# Adafruit_NeoParticle24.net
KiCad netlist of a schematic drawn in EAGLE
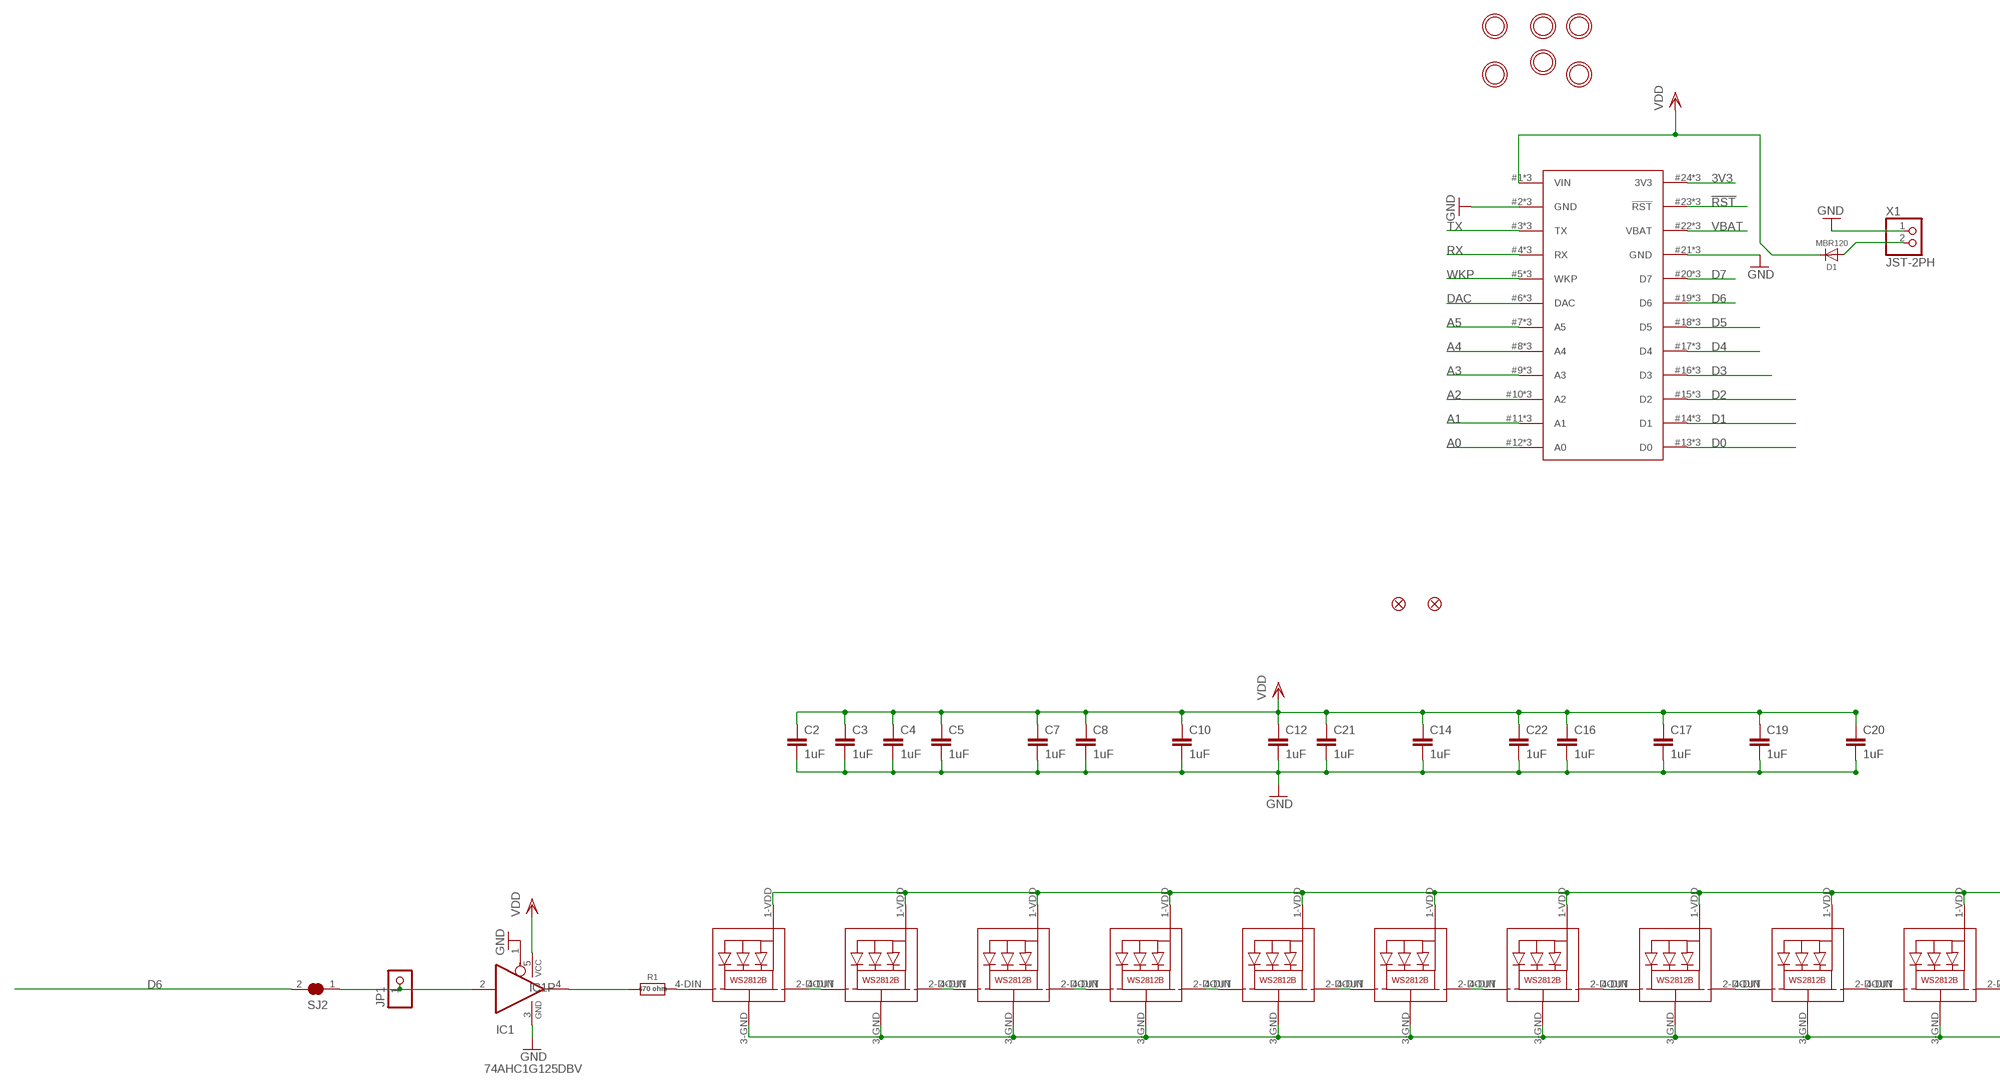
[diagram p0: schematic, sheet 1, part 1 of 2]
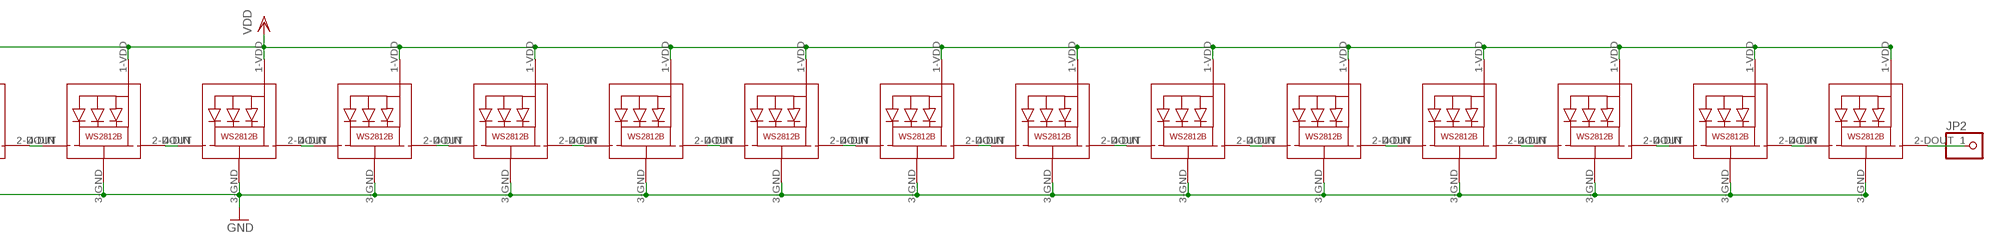
[diagram p1: schematic, sheet 1, part 2 of 2]

(export (version "E")
  (design (tool "Eeschema 10.0.6"))
  (components
    (comp (ref "C2")
      (value "1uF")
      (footprint "eagle-import:C0603")
      (libsource (lib "eagle-import") (part "C-EUC0603"))
    )
    (comp (ref "C3")
      (value "1uF")
      (footprint "eagle-import:C0603")
      (libsource (lib "eagle-import") (part "C-EUC0603"))
    )
    (comp (ref "C4")
      (value "1uF")
      (footprint "eagle-import:C0603")
      (libsource (lib "eagle-import") (part "C-EUC0603"))
    )
    (comp (ref "C5")
      (value "1uF")
      (footprint "eagle-import:C0603")
      (libsource (lib "eagle-import") (part "C-EUC0603"))
    )
    (comp (ref "C7")
      (value "1uF")
      (footprint "eagle-import:C0603")
      (libsource (lib "eagle-import") (part "C-EUC0603"))
    )
    (comp (ref "C8")
      (value "1uF")
      (footprint "eagle-import:C0603")
      (libsource (lib "eagle-import") (part "C-EUC0603"))
    )
    (comp (ref "C10")
      (value "1uF")
      (footprint "eagle-import:C0603")
      (libsource (lib "eagle-import") (part "C-EUC0603"))
    )
    (comp (ref "C12")
      (value "1uF")
      (footprint "eagle-import:C0603")
      (libsource (lib "eagle-import") (part "C-EUC0603"))
    )
    (comp (ref "C14")
      (value "1uF")
      (footprint "eagle-import:C0603")
      (libsource (lib "eagle-import") (part "C-EUC0603"))
    )
    (comp (ref "C16")
      (value "1uF")
      (footprint "eagle-import:C0603")
      (libsource (lib "eagle-import") (part "C-EUC0603"))
    )
    (comp (ref "C17")
      (value "1uF")
      (footprint "eagle-import:C0603")
      (libsource (lib "eagle-import") (part "C-EUC0603"))
    )
    (comp (ref "C19")
      (value "1uF")
      (footprint "eagle-import:C0603")
      (libsource (lib "eagle-import") (part "C-EUC0603"))
    )
    (comp (ref "C20")
      (value "1uF")
      (footprint "eagle-import:C0603")
      (libsource (lib "eagle-import") (part "C-EUC0603"))
    )
    (comp (ref "C21")
      (value "1uF")
      (footprint "eagle-import:C0603")
      (libsource (lib "eagle-import") (part "C-EUC0603"))
    )
    (comp (ref "C22")
      (value "1uF")
      (footprint "eagle-import:C0603")
      (libsource (lib "eagle-import") (part "C-EUC0603"))
    )
    (comp (ref "D1")
      (value "MBR120")
      (footprint "eagle-import:SOD-123")
      (libsource (lib "eagle-import") (part "DIODESOD-123"))
    )
    (comp (ref "FID1")
      (value "FIDUCIAL\"\"")
      (footprint "eagle-import:FIDUCIAL_1MM")
      (libsource (lib "eagle-import") (part "FIDUCIAL{dblquote}{dblquote}"))
    )
    (comp (ref "FID2")
      (value "FIDUCIAL\"\"")
      (footprint "eagle-import:FIDUCIAL_1MM")
      (libsource (lib "eagle-import") (part "FIDUCIAL{dblquote}{dblquote}"))
    )
    (comp (ref "IC1")
      (value "74AHC1G125DBV")
      (footprint "eagle-import:SOT23-5")
      (libsource (lib "eagle-import") (part "741G125DBVAHC"))
    )
    (comp (ref "JP1")
      (value "HEADER-1X1ROUND")
      (footprint "eagle-import:1X01_ROUND")
      (libsource (lib "eagle-import") (part "HEADER-1X1ROUND"))
    )
    (comp (ref "JP2")
      (value "PINHD-1X1CB")
      (footprint "eagle-import:1X01-CLEANBIG")
      (libsource (lib "eagle-import") (part "PINHD-1X1CB"))
    )
    (comp (ref "LED1")
      (value "WS2812B5050")
      (footprint "eagle-import:WS2812B-NARROW")
      (libsource (lib "eagle-import") (part "WS2812B5050-NARROW"))
    )
    (comp (ref "LED2")
      (value "WS2812B5050")
      (footprint "eagle-import:WS2812B-NARROW")
      (libsource (lib "eagle-import") (part "WS2812B5050-NARROW"))
    )
    (comp (ref "LED3")
      (value "WS2812B5050")
      (footprint "eagle-import:WS2812B-NARROW")
      (libsource (lib "eagle-import") (part "WS2812B5050-NARROW"))
    )
    (comp (ref "LED4")
      (value "WS2812B5050")
      (footprint "eagle-import:WS2812B-NARROW")
      (libsource (lib "eagle-import") (part "WS2812B5050-NARROW"))
    )
    (comp (ref "LED5")
      (value "WS2812B5050")
      (footprint "eagle-import:WS2812B-NARROW")
      (libsource (lib "eagle-import") (part "WS2812B5050-NARROW"))
    )
    (comp (ref "LED6")
      (value "WS2812B5050")
      (footprint "eagle-import:WS2812B-NARROW")
      (libsource (lib "eagle-import") (part "WS2812B5050-NARROW"))
    )
    (comp (ref "LED7")
      (value "WS2812B5050")
      (footprint "eagle-import:WS2812B-NARROW")
      (libsource (lib "eagle-import") (part "WS2812B5050-NARROW"))
    )
    (comp (ref "LED8")
      (value "WS2812B5050")
      (footprint "eagle-import:WS2812B-NARROW")
      (libsource (lib "eagle-import") (part "WS2812B5050-NARROW"))
    )
    (comp (ref "LED9")
      (value "WS2812B5050")
      (footprint "eagle-import:WS2812B-NARROW")
      (libsource (lib "eagle-import") (part "WS2812B5050-NARROW"))
    )
    (comp (ref "LED10")
      (value "WS2812B5050")
      (footprint "eagle-import:WS2812B-NARROW")
      (libsource (lib "eagle-import") (part "WS2812B5050-NARROW"))
    )
    (comp (ref "LED11")
      (value "WS2812B5050")
      (footprint "eagle-import:WS2812B-NARROW")
      (libsource (lib "eagle-import") (part "WS2812B5050-NARROW"))
    )
    (comp (ref "LED12")
      (value "WS2812B5050")
      (footprint "eagle-import:WS2812B-NARROW")
      (libsource (lib "eagle-import") (part "WS2812B5050-NARROW"))
    )
    (comp (ref "LED13")
      (value "WS2812B5050")
      (footprint "eagle-import:WS2812B-NARROW")
      (libsource (lib "eagle-import") (part "WS2812B5050-NARROW"))
    )
    (comp (ref "LED14")
      (value "WS2812B5050")
      (footprint "eagle-import:WS2812B-NARROW")
      (libsource (lib "eagle-import") (part "WS2812B5050-NARROW"))
    )
    (comp (ref "LED15")
      (value "WS2812B5050")
      (footprint "eagle-import:WS2812B-NARROW")
      (libsource (lib "eagle-import") (part "WS2812B5050-NARROW"))
    )
    (comp (ref "LED16")
      (value "WS2812B5050")
      (footprint "eagle-import:WS2812B-NARROW")
      (libsource (lib "eagle-import") (part "WS2812B5050-NARROW"))
    )
    (comp (ref "LED17")
      (value "WS2812B5050")
      (footprint "eagle-import:WS2812B-NARROW")
      (libsource (lib "eagle-import") (part "WS2812B5050-NARROW"))
    )
    (comp (ref "LED18")
      (value "WS2812B5050")
      (footprint "eagle-import:WS2812B-NARROW")
      (libsource (lib "eagle-import") (part "WS2812B5050-NARROW"))
    )
    (comp (ref "LED19")
      (value "WS2812B5050")
      (footprint "eagle-import:WS2812B-NARROW")
      (libsource (lib "eagle-import") (part "WS2812B5050-NARROW"))
    )
    (comp (ref "LED20")
      (value "WS2812B5050")
      (footprint "eagle-import:WS2812B-NARROW")
      (libsource (lib "eagle-import") (part "WS2812B5050-NARROW"))
    )
    (comp (ref "LED21")
      (value "WS2812B5050")
      (footprint "eagle-import:WS2812B-NARROW")
      (libsource (lib "eagle-import") (part "WS2812B5050-NARROW"))
    )
    (comp (ref "LED22")
      (value "WS2812B5050")
      (footprint "eagle-import:WS2812B-NARROW")
      (libsource (lib "eagle-import") (part "WS2812B5050-NARROW"))
    )
    (comp (ref "LED23")
      (value "WS2812B5050")
      (footprint "eagle-import:WS2812B-NARROW")
      (libsource (lib "eagle-import") (part "WS2812B5050-NARROW"))
    )
    (comp (ref "LED24")
      (value "WS2812B5050")
      (footprint "eagle-import:WS2812B-NARROW")
      (libsource (lib "eagle-import") (part "WS2812B5050-NARROW"))
    )
    (comp (ref "R1")
      (value "470 ohm")
      (footprint "eagle-import:0603-NO")
      (libsource (lib "eagle-import") (part "RESISTOR_0603_NOOUT"))
    )
    (comp (ref "SJ2")
      (value "SOLDERJUMPER_CLOSED")
      (footprint "eagle-import:SOLDERJUMPER_CLOSEDWIRE")
      (libsource (lib "eagle-import") (part "SOLDERJUMPER_CLOSED"))
    )
    (comp (ref "U$2")
      (value "PHOTON")
      (footprint "eagle-import:SPARK_CORE_STACKABLE")
      (libsource (lib "eagle-import") (part "SPARK_CORE"))
    )
    (comp (ref "U$3")
      (value "MOUNTINGHOLE3.0THIN")
      (footprint "eagle-import:MOUNTINGHOLE_3.0_PLATEDTHIN")
      (libsource (lib "eagle-import") (part "MOUNTINGHOLE3.0THIN"))
    )
    (comp (ref "U$4")
      (value "MOUNTINGHOLE3.0THIN")
      (footprint "eagle-import:MOUNTINGHOLE_3.0_PLATEDTHIN")
      (libsource (lib "eagle-import") (part "MOUNTINGHOLE3.0THIN"))
    )
    (comp (ref "U$5")
      (value "MOUNTINGHOLE3.0THIN")
      (footprint "eagle-import:MOUNTINGHOLE_3.0_PLATEDTHIN")
      (fields (field (name "BOM") "EXCLUDE"))
      (libsource (lib "eagle-import") (part "MOUNTINGHOLE3.0THIN"))
    )
    (comp (ref "U$6")
      (value "MOUNTINGHOLE3.0THIN")
      (footprint "eagle-import:MOUNTINGHOLE_3.0_PLATEDTHIN")
      (fields (field (name "BOM") "EXCLUDE"))
      (libsource (lib "eagle-import") (part "MOUNTINGHOLE3.0THIN"))
    )
    (comp (ref "U$9")
      (value "MOUNTINGHOLE3.0THIN")
      (footprint "eagle-import:MOUNTINGHOLE_3.0_PLATEDTHIN")
      (fields (field (name "BOM") "EXCLUDE"))
      (libsource (lib "eagle-import") (part "MOUNTINGHOLE3.0THIN"))
    )
    (comp (ref "U$10")
      (value "MOUNTINGHOLE3.0THIN")
      (footprint "eagle-import:MOUNTINGHOLE_3.0_PLATEDTHIN")
      (fields (field (name "BOM") "EXCLUDE"))
      (libsource (lib "eagle-import") (part "MOUNTINGHOLE3.0THIN"))
    )
    (comp (ref "X1")
      (value "JST-2PH")
      (footprint "eagle-import:JSTPH2")
      (libsource (lib "eagle-import") (part "CON_JST_PH_2PIN"))
    )
  )
  (nets
    (net (code "1") (name "/3V3") (class "Default")
      (node (ref "U$2") (pin "#24") (pinfunction "3V3_#24") (pintype "power_in"))
      (node (ref "U$2") (pin "24") (pinfunction "3V3_24") (pintype "power_in"))
      (node (ref "U$2") (pin "@24") (pinfunction "3V3_@24") (pintype "power_in"))
    )
    (net (code "2") (name "/A0") (class "Default")
      (node (ref "U$2") (pin "#12") (pinfunction "A0_#12") (pintype "bidirectional"))
      (node (ref "U$2") (pin "12") (pinfunction "A0_12") (pintype "bidirectional"))
      (node (ref "U$2") (pin "@12") (pinfunction "A0_@12") (pintype "bidirectional"))
    )
    (net (code "3") (name "/A1") (class "Default")
      (node (ref "U$2") (pin "#11") (pinfunction "A1_#11") (pintype "bidirectional"))
      (node (ref "U$2") (pin "11") (pinfunction "A1_11") (pintype "bidirectional"))
      (node (ref "U$2") (pin "@11") (pinfunction "A1_@11") (pintype "bidirectional"))
    )
    (net (code "4") (name "/A2") (class "Default")
      (node (ref "U$2") (pin "#10") (pinfunction "A2_#10") (pintype "bidirectional"))
      (node (ref "U$2") (pin "10") (pinfunction "A2_10") (pintype "bidirectional"))
      (node (ref "U$2") (pin "@10") (pinfunction "A2_@10") (pintype "bidirectional"))
    )
    (net (code "5") (name "/A3") (class "Default")
      (node (ref "U$2") (pin "#9") (pinfunction "A3_#9") (pintype "bidirectional"))
      (node (ref "U$2") (pin "9") (pinfunction "A3_9") (pintype "bidirectional"))
      (node (ref "U$2") (pin "@9") (pinfunction "A3_@9") (pintype "bidirectional"))
    )
    (net (code "6") (name "/A4") (class "Default")
      (node (ref "U$2") (pin "#8") (pinfunction "A4_#8") (pintype "bidirectional"))
      (node (ref "U$2") (pin "8") (pinfunction "A4_8") (pintype "bidirectional"))
      (node (ref "U$2") (pin "@8") (pinfunction "A4_@8") (pintype "bidirectional"))
    )
    (net (code "7") (name "/A5") (class "Default")
      (node (ref "U$2") (pin "#7") (pinfunction "A5_#7") (pintype "bidirectional"))
      (node (ref "U$2") (pin "7") (pinfunction "A5_7") (pintype "bidirectional"))
      (node (ref "U$2") (pin "@7") (pinfunction "A5_@7") (pintype "bidirectional"))
    )
    (net (code "8") (name "/D0") (class "Default")
      (node (ref "U$2") (pin "#13") (pinfunction "D0_#13") (pintype "bidirectional"))
      (node (ref "U$2") (pin "13") (pinfunction "D0_13") (pintype "bidirectional"))
      (node (ref "U$2") (pin "@13") (pinfunction "D0_@13") (pintype "bidirectional"))
    )
    (net (code "9") (name "/D1") (class "Default")
      (node (ref "U$2") (pin "#14") (pinfunction "D1_#14") (pintype "bidirectional"))
      (node (ref "U$2") (pin "14") (pinfunction "D1_14") (pintype "bidirectional"))
      (node (ref "U$2") (pin "@14") (pinfunction "D1_@14") (pintype "bidirectional"))
    )
    (net (code "10") (name "/D2") (class "Default")
      (node (ref "U$2") (pin "#15") (pinfunction "D2_#15") (pintype "bidirectional"))
      (node (ref "U$2") (pin "15") (pinfunction "D2_15") (pintype "bidirectional"))
      (node (ref "U$2") (pin "@15") (pinfunction "D2_@15") (pintype "bidirectional"))
    )
    (net (code "11") (name "/D3") (class "Default")
      (node (ref "U$2") (pin "#16") (pinfunction "D3_#16") (pintype "bidirectional"))
      (node (ref "U$2") (pin "16") (pinfunction "D3_16") (pintype "bidirectional"))
      (node (ref "U$2") (pin "@16") (pinfunction "D3_@16") (pintype "bidirectional"))
    )
    (net (code "12") (name "/D4") (class "Default")
      (node (ref "U$2") (pin "#17") (pinfunction "D4_#17") (pintype "bidirectional"))
      (node (ref "U$2") (pin "17") (pinfunction "D4_17") (pintype "bidirectional"))
      (node (ref "U$2") (pin "@17") (pinfunction "D4_@17") (pintype "bidirectional"))
    )
    (net (code "13") (name "/D5") (class "Default")
      (node (ref "U$2") (pin "#18") (pinfunction "D5_#18") (pintype "bidirectional"))
      (node (ref "U$2") (pin "18") (pinfunction "D5_18") (pintype "bidirectional"))
      (node (ref "U$2") (pin "@18") (pinfunction "D5_@18") (pintype "bidirectional"))
    )
    (net (code "14") (name "/D6") (class "Default")
      (node (ref "SJ2") (pin "2") (pinfunction "2_2") (pintype "passive"))
      (node (ref "U$2") (pin "#19") (pinfunction "D6_#19") (pintype "bidirectional"))
      (node (ref "U$2") (pin "19") (pinfunction "D6_19") (pintype "bidirectional"))
      (node (ref "U$2") (pin "@19") (pinfunction "D6_@19") (pintype "bidirectional"))
    )
    (net (code "15") (name "/D7") (class "Default")
      (node (ref "U$2") (pin "#20") (pinfunction "D7_#20") (pintype "bidirectional"))
      (node (ref "U$2") (pin "20") (pinfunction "D7_20") (pintype "bidirectional"))
      (node (ref "U$2") (pin "@20") (pinfunction "D7_@20") (pintype "bidirectional"))
    )
    (net (code "16") (name "/DAC") (class "Default")
      (node (ref "U$2") (pin "#6") (pinfunction "DAC_#6") (pintype "bidirectional"))
      (node (ref "U$2") (pin "6") (pinfunction "DAC_6") (pintype "bidirectional"))
      (node (ref "U$2") (pin "@6") (pinfunction "DAC_@6") (pintype "bidirectional"))
    )
    (net (code "17") (name "/RX") (class "Default")
      (node (ref "U$2") (pin "#4") (pinfunction "RX_#4") (pintype "bidirectional"))
      (node (ref "U$2") (pin "4") (pinfunction "RX_4") (pintype "bidirectional"))
      (node (ref "U$2") (pin "@4") (pinfunction "RX_@4") (pintype "bidirectional"))
    )
    (net (code "18") (name "/TX") (class "Default")
      (node (ref "U$2") (pin "#3") (pinfunction "TX_#3") (pintype "bidirectional"))
      (node (ref "U$2") (pin "3") (pinfunction "TX_3") (pintype "bidirectional"))
      (node (ref "U$2") (pin "@3") (pinfunction "TX_@3") (pintype "bidirectional"))
    )
    (net (code "19") (name "/VBAT") (class "Default")
      (node (ref "U$2") (pin "#22") (pinfunction "VBAT_#22") (pintype "power_in"))
      (node (ref "U$2") (pin "22") (pinfunction "VBAT_22") (pintype "power_in"))
      (node (ref "U$2") (pin "@22") (pinfunction "VBAT_@22") (pintype "power_in"))
    )
    (net (code "20") (name "/WKP") (class "Default")
      (node (ref "U$2") (pin "#5") (pinfunction "WKP_#5") (pintype "bidirectional"))
      (node (ref "U$2") (pin "5") (pinfunction "WKP_5") (pintype "bidirectional"))
      (node (ref "U$2") (pin "@5") (pinfunction "WKP_@5") (pintype "bidirectional"))
    )
    (net (code "21") (name "/~{RST}") (class "Default")
      (node (ref "U$2") (pin "#23") (pinfunction "~{RST}_#23") (pintype "bidirectional"))
      (node (ref "U$2") (pin "23") (pinfunction "~{RST}_23") (pintype "bidirectional"))
      (node (ref "U$2") (pin "@23") (pinfunction "~{RST}_@23") (pintype "bidirectional"))
    )
    (net (code "22") (name "GND") (class "Default")
      (node (ref "C10") (pin "2") (pinfunction "2_2") (pintype "passive"))
      (node (ref "C12") (pin "2") (pinfunction "2_2") (pintype "passive"))
      (node (ref "C14") (pin "2") (pinfunction "2_2") (pintype "passive"))
      (node (ref "C16") (pin "2") (pinfunction "2_2") (pintype "passive"))
      (node (ref "C17") (pin "2") (pinfunction "2_2") (pintype "passive"))
      (node (ref "C19") (pin "2") (pinfunction "2_2") (pintype "passive"))
      (node (ref "C2") (pin "2") (pinfunction "2_2") (pintype "passive"))
      (node (ref "C20") (pin "2") (pinfunction "2_2") (pintype "passive"))
      (node (ref "C21") (pin "2") (pinfunction "2_2") (pintype "passive"))
      (node (ref "C22") (pin "2") (pinfunction "2_2") (pintype "passive"))
      (node (ref "C3") (pin "2") (pinfunction "2_2") (pintype "passive"))
      (node (ref "C4") (pin "2") (pinfunction "2_2") (pintype "passive"))
      (node (ref "C5") (pin "2") (pinfunction "2_2") (pintype "passive"))
      (node (ref "C7") (pin "2") (pinfunction "2_2") (pintype "passive"))
      (node (ref "C8") (pin "2") (pinfunction "2_2") (pintype "passive"))
      (node (ref "IC1") (pin "1") (pinfunction "OE_1") (pintype "input"))
      (node (ref "IC1") (pin "3") (pinfunction "GND_3") (pintype "power_in"))
      (node (ref "LED1") (pin "3-GND") (pinfunction "GND_3-GND") (pintype "power_in"))
      (node (ref "LED10") (pin "3-GND") (pinfunction "GND_3-GND") (pintype "power_in"))
      (node (ref "LED11") (pin "3-GND") (pinfunction "GND_3-GND") (pintype "power_in"))
      (node (ref "LED12") (pin "3-GND") (pinfunction "GND_3-GND") (pintype "power_in"))
      (node (ref "LED13") (pin "3-GND") (pinfunction "GND_3-GND") (pintype "power_in"))
      (node (ref "LED14") (pin "3-GND") (pinfunction "GND_3-GND") (pintype "power_in"))
      (node (ref "LED15") (pin "3-GND") (pinfunction "GND_3-GND") (pintype "power_in"))
      (node (ref "LED16") (pin "3-GND") (pinfunction "GND_3-GND") (pintype "power_in"))
      (node (ref "LED17") (pin "3-GND") (pinfunction "GND_3-GND") (pintype "power_in"))
      (node (ref "LED18") (pin "3-GND") (pinfunction "GND_3-GND") (pintype "power_in"))
      (node (ref "LED19") (pin "3-GND") (pinfunction "GND_3-GND") (pintype "power_in"))
      (node (ref "LED2") (pin "3-GND") (pinfunction "GND_3-GND") (pintype "power_in"))
      (node (ref "LED20") (pin "3-GND") (pinfunction "GND_3-GND") (pintype "power_in"))
      (node (ref "LED21") (pin "3-GND") (pinfunction "GND_3-GND") (pintype "power_in"))
      (node (ref "LED22") (pin "3-GND") (pinfunction "GND_3-GND") (pintype "power_in"))
      (node (ref "LED23") (pin "3-GND") (pinfunction "GND_3-GND") (pintype "power_in"))
      (node (ref "LED24") (pin "3-GND") (pinfunction "GND_3-GND") (pintype "power_in"))
      (node (ref "LED3") (pin "3-GND") (pinfunction "GND_3-GND") (pintype "power_in"))
      (node (ref "LED4") (pin "3-GND") (pinfunction "GND_3-GND") (pintype "power_in"))
      (node (ref "LED5") (pin "3-GND") (pinfunction "GND_3-GND") (pintype "power_in"))
      (node (ref "LED6") (pin "3-GND") (pinfunction "GND_3-GND") (pintype "power_in"))
      (node (ref "LED7") (pin "3-GND") (pinfunction "GND_3-GND") (pintype "power_in"))
      (node (ref "LED8") (pin "3-GND") (pinfunction "GND_3-GND") (pintype "power_in"))
      (node (ref "LED9") (pin "3-GND") (pinfunction "GND_3-GND") (pintype "power_in"))
      (node (ref "U$2") (pin "#2") (pinfunction "GND_#2") (pintype "power_in"))
      (node (ref "U$2") (pin "#21") (pinfunction "GND_#21") (pintype "power_in"))
      (node (ref "U$2") (pin "2") (pinfunction "GND_2") (pintype "power_in"))
      (node (ref "U$2") (pin "21") (pinfunction "GND_21") (pintype "power_in"))
      (node (ref "U$2") (pin "@2") (pinfunction "GND_@2") (pintype "power_in"))
      (node (ref "U$2") (pin "@21") (pinfunction "GND_@21") (pintype "power_in"))
      (node (ref "X1") (pin "1") (pinfunction "1_1") (pintype "passive"))
    )
    (net (code "23") (name "Net-(D1-PadA)") (class "Default")
      (node (ref "D1") (pin "A") (pinfunction "A_A") (pintype "passive"))
      (node (ref "X1") (pin "2") (pinfunction "2_2") (pintype "passive"))
    )
    (net (code "24") (name "Net-(IC1A-I)") (class "Default")
      (node (ref "IC1") (pin "2") (pinfunction "I_2") (pintype "input"))
      (node (ref "JP1") (pin "1") (pinfunction "1_1") (pintype "passive"))
      (node (ref "SJ2") (pin "1") (pinfunction "1_1") (pintype "passive"))
    )
    (net (code "25") (name "Net-(IC1A-O)") (class "Default")
      (node (ref "IC1") (pin "4") (pinfunction "O_4") (pintype "tri_state"))
      (node (ref "R1") (pin "1") (pinfunction "1_1") (pintype "passive"))
    )
    (net (code "26") (name "Net-(LED1-DI)") (class "Default")
      (node (ref "LED1") (pin "4-DIN") (pinfunction "DI_4-DIN") (pintype "input"))
      (node (ref "R1") (pin "2") (pinfunction "2_2") (pintype "passive"))
    )
    (net (code "27") (name "Net-(LED1-DO)") (class "Default")
      (node (ref "LED1") (pin "2-DOUT") (pinfunction "DO_2-DOUT") (pintype "output"))
      (node (ref "LED2") (pin "4-DIN") (pinfunction "DI_4-DIN") (pintype "input"))
    )
    (net (code "28") (name "Net-(LED2-DO)") (class "Default")
      (node (ref "LED2") (pin "2-DOUT") (pinfunction "DO_2-DOUT") (pintype "output"))
      (node (ref "LED3") (pin "4-DIN") (pinfunction "DI_4-DIN") (pintype "input"))
    )
    (net (code "29") (name "Net-(LED3-DO)") (class "Default")
      (node (ref "LED3") (pin "2-DOUT") (pinfunction "DO_2-DOUT") (pintype "output"))
      (node (ref "LED4") (pin "4-DIN") (pinfunction "DI_4-DIN") (pintype "input"))
    )
    (net (code "30") (name "Net-(LED4-DO)") (class "Default")
      (node (ref "LED4") (pin "2-DOUT") (pinfunction "DO_2-DOUT") (pintype "output"))
      (node (ref "LED5") (pin "4-DIN") (pinfunction "DI_4-DIN") (pintype "input"))
    )
    (net (code "31") (name "Net-(LED5-DO)") (class "Default")
      (node (ref "LED5") (pin "2-DOUT") (pinfunction "DO_2-DOUT") (pintype "output"))
      (node (ref "LED6") (pin "4-DIN") (pinfunction "DI_4-DIN") (pintype "input"))
    )
    (net (code "32") (name "Net-(LED6-DO)") (class "Default")
      (node (ref "LED6") (pin "2-DOUT") (pinfunction "DO_2-DOUT") (pintype "output"))
      (node (ref "LED7") (pin "4-DIN") (pinfunction "DI_4-DIN") (pintype "input"))
    )
    (net (code "33") (name "Net-(LED7-DO)") (class "Default")
      (node (ref "LED7") (pin "2-DOUT") (pinfunction "DO_2-DOUT") (pintype "output"))
      (node (ref "LED8") (pin "4-DIN") (pinfunction "DI_4-DIN") (pintype "input"))
    )
    (net (code "34") (name "Net-(LED8-DO)") (class "Default")
      (node (ref "LED8") (pin "2-DOUT") (pinfunction "DO_2-DOUT") (pintype "output"))
      (node (ref "LED9") (pin "4-DIN") (pinfunction "DI_4-DIN") (pintype "input"))
    )
    (net (code "35") (name "Net-(LED10-DI)") (class "Default")
      (node (ref "LED10") (pin "4-DIN") (pinfunction "DI_4-DIN") (pintype "input"))
      (node (ref "LED9") (pin "2-DOUT") (pinfunction "DO_2-DOUT") (pintype "output"))
    )
    (net (code "36") (name "Net-(LED10-DO)") (class "Default")
      (node (ref "LED10") (pin "2-DOUT") (pinfunction "DO_2-DOUT") (pintype "output"))
      (node (ref "LED11") (pin "4-DIN") (pinfunction "DI_4-DIN") (pintype "input"))
    )
    (net (code "37") (name "Net-(LED11-DO)") (class "Default")
      (node (ref "LED11") (pin "2-DOUT") (pinfunction "DO_2-DOUT") (pintype "output"))
      (node (ref "LED12") (pin "4-DIN") (pinfunction "DI_4-DIN") (pintype "input"))
    )
    (net (code "38") (name "Net-(LED12-DO)") (class "Default")
      (node (ref "LED12") (pin "2-DOUT") (pinfunction "DO_2-DOUT") (pintype "output"))
      (node (ref "LED13") (pin "4-DIN") (pinfunction "DI_4-DIN") (pintype "input"))
    )
    (net (code "39") (name "Net-(LED13-DO)") (class "Default")
      (node (ref "LED13") (pin "2-DOUT") (pinfunction "DO_2-DOUT") (pintype "output"))
      (node (ref "LED14") (pin "4-DIN") (pinfunction "DI_4-DIN") (pintype "input"))
    )
    (net (code "40") (name "Net-(LED14-DO)") (class "Default")
      (node (ref "LED14") (pin "2-DOUT") (pinfunction "DO_2-DOUT") (pintype "output"))
      (node (ref "LED15") (pin "4-DIN") (pinfunction "DI_4-DIN") (pintype "input"))
    )
    (net (code "41") (name "Net-(LED15-DO)") (class "Default")
      (node (ref "LED15") (pin "2-DOUT") (pinfunction "DO_2-DOUT") (pintype "output"))
      (node (ref "LED16") (pin "4-DIN") (pinfunction "DI_4-DIN") (pintype "input"))
    )
    (net (code "42") (name "Net-(LED16-DO)") (class "Default")
      (node (ref "LED16") (pin "2-DOUT") (pinfunction "DO_2-DOUT") (pintype "output"))
      (node (ref "LED17") (pin "4-DIN") (pinfunction "DI_4-DIN") (pintype "input"))
    )
    (net (code "43") (name "Net-(LED17-DO)") (class "Default")
      (node (ref "LED17") (pin "2-DOUT") (pinfunction "DO_2-DOUT") (pintype "output"))
      (node (ref "LED18") (pin "4-DIN") (pinfunction "DI_4-DIN") (pintype "input"))
    )
    (net (code "44") (name "Net-(LED18-DO)") (class "Default")
      (node (ref "LED18") (pin "2-DOUT") (pinfunction "DO_2-DOUT") (pintype "output"))
      (node (ref "LED19") (pin "4-DIN") (pinfunction "DI_4-DIN") (pintype "input"))
    )
    (net (code "45") (name "Net-(LED19-DO)") (class "Default")
      (node (ref "LED19") (pin "2-DOUT") (pinfunction "DO_2-DOUT") (pintype "output"))
      (node (ref "LED20") (pin "4-DIN") (pinfunction "DI_4-DIN") (pintype "input"))
    )
    (net (code "46") (name "Net-(LED20-DO)") (class "Default")
      (node (ref "LED20") (pin "2-DOUT") (pinfunction "DO_2-DOUT") (pintype "output"))
      (node (ref "LED21") (pin "4-DIN") (pinfunction "DI_4-DIN") (pintype "input"))
    )
    (net (code "47") (name "Net-(LED21-DO)") (class "Default")
      (node (ref "LED21") (pin "2-DOUT") (pinfunction "DO_2-DOUT") (pintype "output"))
      (node (ref "LED22") (pin "4-DIN") (pinfunction "DI_4-DIN") (pintype "input"))
    )
    (net (code "48") (name "Net-(LED22-DO)") (class "Default")
      (node (ref "LED22") (pin "2-DOUT") (pinfunction "DO_2-DOUT") (pintype "output"))
      (node (ref "LED23") (pin "4-DIN") (pinfunction "DI_4-DIN") (pintype "input"))
    )
    (net (code "49") (name "Net-(LED23-DO)") (class "Default")
      (node (ref "LED23") (pin "2-DOUT") (pinfunction "DO_2-DOUT") (pintype "output"))
      (node (ref "LED24") (pin "4-DIN") (pinfunction "DI_4-DIN") (pintype "input"))
    )
    (net (code "50") (name "Net-(LED24-DO)") (class "Default")
      (node (ref "JP2") (pin "1") (pinfunction "1_1") (pintype "passive"))
      (node (ref "LED24") (pin "2-DOUT") (pinfunction "DO_2-DOUT") (pintype "output"))
    )
    (net (code "51") (name "VDD") (class "Default")
      (node (ref "C10") (pin "1") (pinfunction "1_1") (pintype "passive"))
      (node (ref "C12") (pin "1") (pinfunction "1_1") (pintype "passive"))
      (node (ref "C14") (pin "1") (pinfunction "1_1") (pintype "passive"))
      (node (ref "C16") (pin "1") (pinfunction "1_1") (pintype "passive"))
      (node (ref "C17") (pin "1") (pinfunction "1_1") (pintype "passive"))
      (node (ref "C19") (pin "1") (pinfunction "1_1") (pintype "passive"))
      (node (ref "C2") (pin "1") (pinfunction "1_1") (pintype "passive"))
      (node (ref "C20") (pin "1") (pinfunction "1_1") (pintype "passive"))
      (node (ref "C21") (pin "1") (pinfunction "1_1") (pintype "passive"))
      (node (ref "C22") (pin "1") (pinfunction "1_1") (pintype "passive"))
      (node (ref "C3") (pin "1") (pinfunction "1_1") (pintype "passive"))
      (node (ref "C4") (pin "1") (pinfunction "1_1") (pintype "passive"))
      (node (ref "C5") (pin "1") (pinfunction "1_1") (pintype "passive"))
      (node (ref "C7") (pin "1") (pinfunction "1_1") (pintype "passive"))
      (node (ref "C8") (pin "1") (pinfunction "1_1") (pintype "passive"))
      (node (ref "D1") (pin "C") (pinfunction "C_C") (pintype "passive"))
      (node (ref "IC1") (pin "5") (pinfunction "VCC_5") (pintype "power_in"))
      (node (ref "LED1") (pin "1-VDD") (pinfunction "VDD_1-VDD") (pintype "power_in"))
      (node (ref "LED10") (pin "1-VDD") (pinfunction "VDD_1-VDD") (pintype "power_in"))
      (node (ref "LED11") (pin "1-VDD") (pinfunction "VDD_1-VDD") (pintype "power_in"))
      (node (ref "LED12") (pin "1-VDD") (pinfunction "VDD_1-VDD") (pintype "power_in"))
      (node (ref "LED13") (pin "1-VDD") (pinfunction "VDD_1-VDD") (pintype "power_in"))
      (node (ref "LED14") (pin "1-VDD") (pinfunction "VDD_1-VDD") (pintype "power_in"))
      (node (ref "LED15") (pin "1-VDD") (pinfunction "VDD_1-VDD") (pintype "power_in"))
      (node (ref "LED16") (pin "1-VDD") (pinfunction "VDD_1-VDD") (pintype "power_in"))
      (node (ref "LED17") (pin "1-VDD") (pinfunction "VDD_1-VDD") (pintype "power_in"))
      (node (ref "LED18") (pin "1-VDD") (pinfunction "VDD_1-VDD") (pintype "power_in"))
      (node (ref "LED19") (pin "1-VDD") (pinfunction "VDD_1-VDD") (pintype "power_in"))
      (node (ref "LED2") (pin "1-VDD") (pinfunction "VDD_1-VDD") (pintype "power_in"))
      (node (ref "LED20") (pin "1-VDD") (pinfunction "VDD_1-VDD") (pintype "power_in"))
      (node (ref "LED21") (pin "1-VDD") (pinfunction "VDD_1-VDD") (pintype "power_in"))
      (node (ref "LED22") (pin "1-VDD") (pinfunction "VDD_1-VDD") (pintype "power_in"))
      (node (ref "LED23") (pin "1-VDD") (pinfunction "VDD_1-VDD") (pintype "power_in"))
      (node (ref "LED24") (pin "1-VDD") (pinfunction "VDD_1-VDD") (pintype "power_in"))
      (node (ref "LED3") (pin "1-VDD") (pinfunction "VDD_1-VDD") (pintype "power_in"))
      (node (ref "LED4") (pin "1-VDD") (pinfunction "VDD_1-VDD") (pintype "power_in"))
      (node (ref "LED5") (pin "1-VDD") (pinfunction "VDD_1-VDD") (pintype "power_in"))
      (node (ref "LED6") (pin "1-VDD") (pinfunction "VDD_1-VDD") (pintype "power_in"))
      (node (ref "LED7") (pin "1-VDD") (pinfunction "VDD_1-VDD") (pintype "power_in"))
      (node (ref "LED8") (pin "1-VDD") (pinfunction "VDD_1-VDD") (pintype "power_in"))
      (node (ref "LED9") (pin "1-VDD") (pinfunction "VDD_1-VDD") (pintype "power_in"))
      (node (ref "U$2") (pin "#1") (pinfunction "VIN_#1") (pintype "power_in"))
      (node (ref "U$2") (pin "1") (pinfunction "VIN_1") (pintype "power_in"))
      (node (ref "U$2") (pin "@1") (pinfunction "VIN_@1") (pintype "power_in"))
    )
  )
)
